# H-Bridge.net
KiCad netlist of a schematic drawn in EAGLE
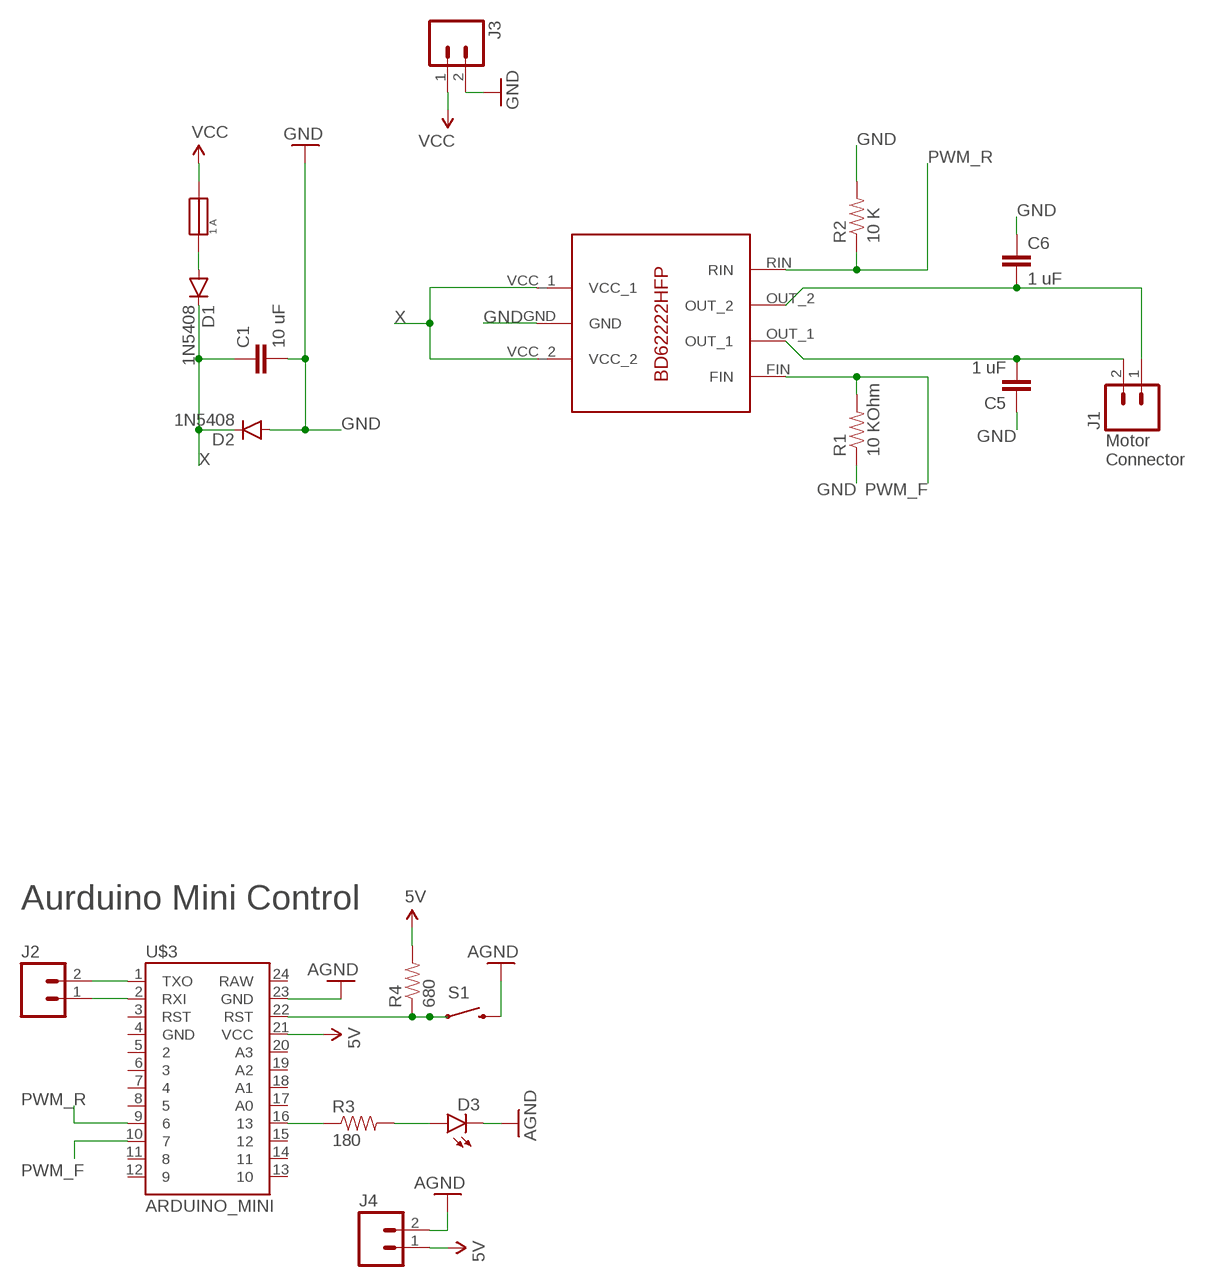
[diagram p0: schematic, sheet 1]

(export (version "E")
  (design (tool "Eeschema 10.0.6"))
  (components
    (comp (ref "C1")
      (value "10 uF")
      (footprint "eagle-import:0805")
      (libsource (lib "eagle-import") (part "CAP0805"))
    )
    (comp (ref "C5")
      (value "1 uF")
      (footprint "eagle-import:0805")
      (libsource (lib "eagle-import") (part "CAP0805"))
    )
    (comp (ref "C6")
      (value "1 uF")
      (footprint "eagle-import:0805")
      (libsource (lib "eagle-import") (part "CAP0805"))
    )
    (comp (ref "D1")
      (value "1N5408")
      (footprint "eagle-import:DIODE-1N4148")
      (libsource (lib "eagle-import") (part "DIODE1N4148"))
    )
    (comp (ref "D2")
      (value "1N5408")
      (footprint "eagle-import:DIODE-1N4148")
      (libsource (lib "eagle-import") (part "DIODE1N4148"))
    )
    (comp (ref "D3")
      (value "LED3MM")
      (footprint "eagle-import:LED3MM")
      (libsource (lib "eagle-import") (part "LED3MM"))
    )
    (comp (ref "J1")
      (value "M023.5MM")
      (footprint "eagle-import:SCREWTERMINAL-3.5MM-2")
      (libsource (lib "eagle-import") (part "M023.5MM"))
    )
    (comp (ref "J2")
      (value "M02LOCK")
      (footprint "eagle-import:1X02_LOCK")
      (libsource (lib "eagle-import") (part "M02LOCK"))
    )
    (comp (ref "J3")
      (value "M023.5MM")
      (footprint "eagle-import:SCREWTERMINAL-3.5MM-2")
      (libsource (lib "eagle-import") (part "M023.5MM"))
    )
    (comp (ref "J4")
      (value "M023.5MM")
      (footprint "eagle-import:SCREWTERMINAL-3.5MM-2")
      (libsource (lib "eagle-import") (part "M023.5MM"))
    )
    (comp (ref "R1")
      (value "10 KOhm")
      (footprint "eagle-import:1_6W-RES")
      (libsource (lib "eagle-import") (part "RESISTORPTH-1/6W"))
    )
    (comp (ref "R2")
      (value "10 K")
      (footprint "eagle-import:1_6W-RES")
      (libsource (lib "eagle-import") (part "RESISTORPTH-1/6W"))
    )
    (comp (ref "R3")
      (value "180")
      (footprint "eagle-import:AXIAL-0.3")
      (libsource (lib "eagle-import") (part "RESISTORAXIAL-0.3"))
    )
    (comp (ref "R4")
      (value "680")
      (footprint "eagle-import:AXIAL-0.3")
      (libsource (lib "eagle-import") (part "RESISTORAXIAL-0.3"))
    )
    (comp (ref "S1")
      (value "SWITCH-MOMENTARY-2PTH")
      (footprint "eagle-import:TACTILE-PTH")
      (libsource (lib "eagle-import") (part "SWITCH-MOMENTARY-2PTH"))
    )
    (comp (ref "U$1")
      (value "BD62222HFP")
      (footprint "eagle-import:BD62222HFP")
      (libsource (lib "eagle-import") (part "BD62222HFP"))
    )
    (comp (ref "U$3")
      (value "ARDUINO_MINI")
      (footprint "eagle-import:ARDUINO_MINI")
      (libsource (lib "eagle-import") (part "ARDUINO_MINI"))
    )
    (comp (ref "U$8")
      (value "1 A")
      (footprint "eagle-import:5MM_PC_FUSE_HOLDER_KEYSTONE_ELEC")
      (libsource (lib "eagle-import") (part "5MM_PC_FUSE_HOLDER_KEYSTONE_ELEC"))
    )
  )
  (nets
    (net (code "1") (name "/PWM_F") (class "Default")
      (node (ref "R1") (pin "2") (pinfunction "2_2") (pintype "passive"))
      (node (ref "U$1") (pin "FIN") (pinfunction "FIN_FIN") (pintype "bidirectional"))
      (node (ref "U$3") (pin "10") (pinfunction "7_10") (pintype "bidirectional"))
    )
    (net (code "2") (name "/PWM_R") (class "Default")
      (node (ref "R2") (pin "1") (pinfunction "1_1") (pintype "passive"))
      (node (ref "U$1") (pin "RIN") (pinfunction "RIN_RIN") (pintype "bidirectional"))
      (node (ref "U$3") (pin "9") (pinfunction "6_9") (pintype "bidirectional"))
    )
    (net (code "3") (name "/X") (class "Default")
      (node (ref "C1") (pin "1") (pinfunction "1_1") (pintype "passive"))
      (node (ref "D1") (pin "C") (pinfunction "C_C") (pintype "passive"))
      (node (ref "D2") (pin "C") (pinfunction "C_C") (pintype "passive"))
      (node (ref "U$1") (pin "VCC_1") (pinfunction "VCC_1_VCC_1") (pintype "bidirectional"))
      (node (ref "U$1") (pin "VCC_2") (pinfunction "VCC_2_VCC_2") (pintype "bidirectional"))
    )
    (net (code "4") (name "5V") (class "Default")
      (node (ref "J4") (pin "1") (pinfunction "1_1") (pintype "passive"))
      (node (ref "R4") (pin "P$2") (pinfunction "2_P$2") (pintype "passive"))
      (node (ref "U$3") (pin "21") (pinfunction "VCC_21") (pintype "bidirectional"))
    )
    (net (code "5") (name "AGND") (class "Default")
      (node (ref "D3") (pin "K") (pinfunction "C_K") (pintype "passive"))
      (node (ref "J4") (pin "2") (pinfunction "2_2") (pintype "passive"))
      (node (ref "S1") (pin "3") (pinfunction "2_3") (pintype "passive"))
      (node (ref "U$3") (pin "23") (pinfunction "GND_23") (pintype "bidirectional"))
    )
    (net (code "6") (name "GND") (class "Default")
      (node (ref "C1") (pin "2") (pinfunction "2_2") (pintype "passive"))
      (node (ref "C5") (pin "1") (pinfunction "1_1") (pintype "passive"))
      (node (ref "C6") (pin "1") (pinfunction "1_1") (pintype "passive"))
      (node (ref "D2") (pin "A") (pinfunction "A_A") (pintype "passive"))
      (node (ref "J3") (pin "2") (pinfunction "2_2") (pintype "passive"))
      (node (ref "R1") (pin "1") (pinfunction "1_1") (pintype "passive"))
      (node (ref "R2") (pin "2") (pinfunction "2_2") (pintype "passive"))
      (node (ref "U$1") (pin "GND") (pinfunction "GND_GND") (pintype "bidirectional"))
    )
    (net (code "7") (name "Net-(C5-Pad2)") (class "Default")
      (node (ref "C5") (pin "2") (pinfunction "2_2") (pintype "passive"))
      (node (ref "J1") (pin "2") (pinfunction "2_2") (pintype "passive"))
      (node (ref "U$1") (pin "OUT_1") (pinfunction "OUT_1_OUT_1") (pintype "bidirectional"))
    )
    (net (code "8") (name "Net-(C6-Pad2)") (class "Default")
      (node (ref "C6") (pin "2") (pinfunction "2_2") (pintype "passive"))
      (node (ref "J1") (pin "1") (pinfunction "1_1") (pintype "passive"))
      (node (ref "U$1") (pin "OUT_2") (pinfunction "OUT_2_OUT_2") (pintype "bidirectional"))
    )
    (net (code "9") (name "Net-(D1-PadA)") (class "Default")
      (node (ref "D1") (pin "A") (pinfunction "A_A") (pintype "passive"))
      (node (ref "U$8") (pin "P$2") (pinfunction "P$2_P$2") (pintype "bidirectional"))
    )
    (net (code "10") (name "Net-(R3-1)") (class "Default")
      (node (ref "R3") (pin "P$1") (pinfunction "1_P$1") (pintype "passive"))
      (node (ref "U$3") (pin "16") (pinfunction "13_16") (pintype "bidirectional"))
    )
    (net (code "11") (name "Net-(R3-2)") (class "Default")
      (node (ref "D3") (pin "A") (pinfunction "A_A") (pintype "passive"))
      (node (ref "R3") (pin "P$2") (pinfunction "2_P$2") (pintype "passive"))
    )
    (net (code "12") (name "Net-(R4-1)") (class "Default")
      (node (ref "R4") (pin "P$1") (pinfunction "1_P$1") (pintype "passive"))
      (node (ref "S1") (pin "1") (pinfunction "1_1") (pintype "passive"))
      (node (ref "U$3") (pin "22") (pinfunction "RST_22") (pintype "bidirectional"))
    )
    (net (code "13") (name "Net-(U$3-RXI)") (class "Default")
      (node (ref "J2") (pin "1") (pinfunction "1_1") (pintype "passive"))
      (node (ref "U$3") (pin "2") (pinfunction "RXI_2") (pintype "bidirectional"))
    )
    (net (code "14") (name "Net-(U$3-TXO)") (class "Default")
      (node (ref "J2") (pin "2") (pinfunction "2_2") (pintype "passive"))
      (node (ref "U$3") (pin "1") (pinfunction "TXO_1") (pintype "bidirectional"))
    )
    (net (code "15") (name "VCC") (class "Default")
      (node (ref "J3") (pin "1") (pinfunction "1_1") (pintype "passive"))
      (node (ref "U$8") (pin "P$1") (pinfunction "P$1_P$1") (pintype "bidirectional"))
    )
    (net (code "16") (name "unconnected-(U$3-2-Pad5)") (class "Default")
      (node (ref "U$3") (pin "5") (pinfunction "2_5") (pintype "bidirectional"))
    )
    (net (code "17") (name "unconnected-(U$3-3-Pad6)") (class "Default")
      (node (ref "U$3") (pin "6") (pinfunction "3_6") (pintype "bidirectional"))
    )
    (net (code "18") (name "unconnected-(U$3-4-Pad7)") (class "Default")
      (node (ref "U$3") (pin "7") (pinfunction "4_7") (pintype "bidirectional"))
    )
    (net (code "19") (name "unconnected-(U$3-5-Pad8)") (class "Default")
      (node (ref "U$3") (pin "8") (pinfunction "5_8") (pintype "bidirectional"))
    )
    (net (code "20") (name "unconnected-(U$3-8-Pad11)") (class "Default")
      (node (ref "U$3") (pin "11") (pinfunction "8_11") (pintype "bidirectional"))
    )
    (net (code "21") (name "unconnected-(U$3-9-Pad12)") (class "Default")
      (node (ref "U$3") (pin "12") (pinfunction "9_12") (pintype "bidirectional"))
    )
    (net (code "22") (name "unconnected-(U$3-10-Pad13)") (class "Default")
      (node (ref "U$3") (pin "13") (pinfunction "10_13") (pintype "bidirectional"))
    )
    (net (code "23") (name "unconnected-(U$3-11-Pad14)") (class "Default")
      (node (ref "U$3") (pin "14") (pinfunction "11_14") (pintype "bidirectional"))
    )
    (net (code "24") (name "unconnected-(U$3-12-Pad15)") (class "Default")
      (node (ref "U$3") (pin "15") (pinfunction "12_15") (pintype "bidirectional"))
    )
    (net (code "25") (name "unconnected-(U$3-A0-Pad17)") (class "Default")
      (node (ref "U$3") (pin "17") (pinfunction "A0_17") (pintype "bidirectional"))
    )
    (net (code "26") (name "unconnected-(U$3-A1-Pad18)") (class "Default")
      (node (ref "U$3") (pin "18") (pinfunction "A1_18") (pintype "bidirectional"))
    )
    (net (code "27") (name "unconnected-(U$3-A2-Pad19)") (class "Default")
      (node (ref "U$3") (pin "19") (pinfunction "A2_19") (pintype "bidirectional"))
    )
    (net (code "28") (name "unconnected-(U$3-A3-Pad20)") (class "Default")
      (node (ref "U$3") (pin "20") (pinfunction "A3_20") (pintype "bidirectional"))
    )
    (net (code "29") (name "unconnected-(U$3-GND-Pad4)") (class "Default")
      (node (ref "U$3") (pin "4") (pinfunction "GND_4") (pintype "bidirectional"))
    )
    (net (code "30") (name "unconnected-(U$3-RAW-Pad24)") (class "Default")
      (node (ref "U$3") (pin "24") (pinfunction "RAW_24") (pintype "bidirectional"))
    )
    (net (code "31") (name "unconnected-(U$3-RST-Pad3)") (class "Default")
      (node (ref "U$3") (pin "3") (pinfunction "RST_3") (pintype "bidirectional"))
    )
  )
)
